# Disp_Eye.net
KiCad netlist of a schematic drawn in Altium Designer
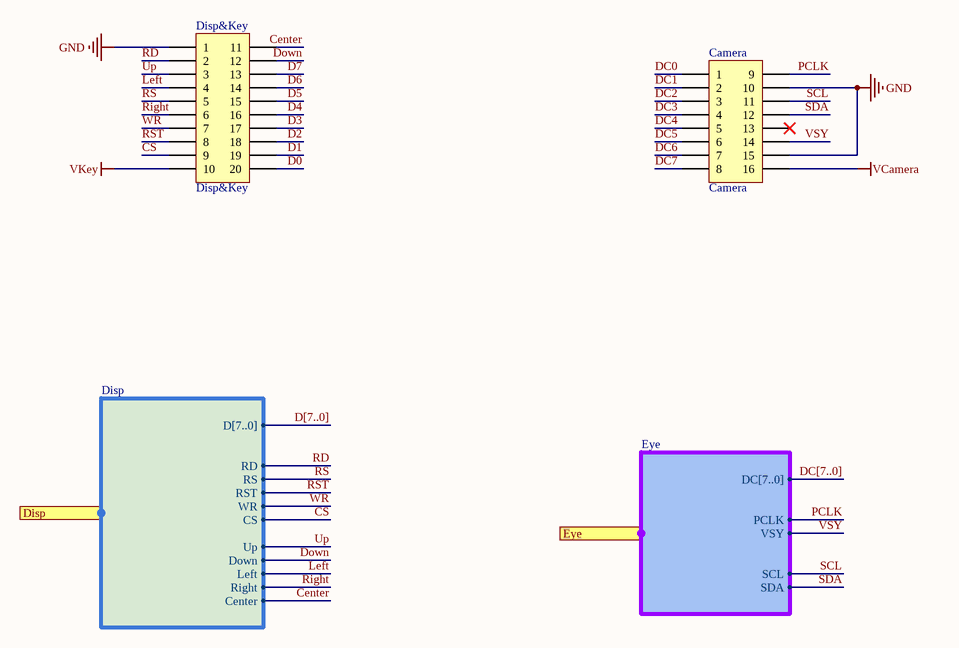
[diagram p0: Disp&Eye.SchDoc]

(export (version "E")
  (design (tool "Eeschema 10.0.6"))
  (components
    (comp (ref "Camera")
      (value "Camera")
      (footprint "HDR2X8_CEN")
      (description "Header, 8-Pin, Dual row")
      (fields (field (name "PUBLISHER") "Altium Limited"))
      (libsource (lib "Miscellaneous Connectors") (part "Header 8X2A"))
    )
    (comp (ref "Disp&Key")
      (value "Disp&Key")
      (footprint "HDR2X10_CEN")
      (description "Header, 10-Pin, Dual row")
      (fields (field (name "PUBLISHER") "Altium Limited"))
      (libsource (lib "Miscellaneous Connectors") (part "Header 10X2A"))
    )
  )
  (nets
    (net (code "3") (name "/CS") (class "Default")
      (node (ref "Disp&Key") (pin "9") (pinfunction "9_9") (pintype "passive"))
    )
    (net (code "4") (name "/Center") (class "Default")
      (node (ref "Disp&Key") (pin "11") (pinfunction "11_11") (pintype "passive"))
    )
    (net (code "5") (name "/D0") (class "Default")
      (node (ref "Disp&Key") (pin "20") (pinfunction "20_20") (pintype "passive"))
    )
    (net (code "6") (name "/D1") (class "Default")
      (node (ref "Disp&Key") (pin "19") (pinfunction "19_19") (pintype "passive"))
    )
    (net (code "7") (name "/D2") (class "Default")
      (node (ref "Disp&Key") (pin "18") (pinfunction "18_18") (pintype "passive"))
    )
    (net (code "8") (name "/D3") (class "Default")
      (node (ref "Disp&Key") (pin "17") (pinfunction "17_17") (pintype "passive"))
    )
    (net (code "9") (name "/D4") (class "Default")
      (node (ref "Disp&Key") (pin "16") (pinfunction "16_16") (pintype "passive"))
    )
    (net (code "10") (name "/D5") (class "Default")
      (node (ref "Disp&Key") (pin "15") (pinfunction "15_15") (pintype "passive"))
    )
    (net (code "11") (name "/D6") (class "Default")
      (node (ref "Disp&Key") (pin "14") (pinfunction "14_14") (pintype "passive"))
    )
    (net (code "12") (name "/D7") (class "Default")
      (node (ref "Disp&Key") (pin "13") (pinfunction "13_13") (pintype "passive"))
    )
    (net (code "13") (name "/DC0") (class "Default")
      (node (ref "Camera") (pin "1") (pinfunction "1_1") (pintype "passive"))
    )
    (net (code "14") (name "/DC1") (class "Default")
      (node (ref "Camera") (pin "2") (pinfunction "2_2") (pintype "passive"))
    )
    (net (code "15") (name "/DC2") (class "Default")
      (node (ref "Camera") (pin "3") (pinfunction "3_3") (pintype "passive"))
    )
    (net (code "16") (name "/DC3") (class "Default")
      (node (ref "Camera") (pin "4") (pinfunction "4_4") (pintype "passive"))
    )
    (net (code "17") (name "/DC4") (class "Default")
      (node (ref "Camera") (pin "5") (pinfunction "5_5") (pintype "passive"))
    )
    (net (code "18") (name "/DC5") (class "Default")
      (node (ref "Camera") (pin "6") (pinfunction "6_6") (pintype "passive"))
    )
    (net (code "19") (name "/DC6") (class "Default")
      (node (ref "Camera") (pin "7") (pinfunction "7_7") (pintype "passive"))
    )
    (net (code "20") (name "/DC7") (class "Default")
      (node (ref "Camera") (pin "8") (pinfunction "8_8") (pintype "passive"))
    )
    (net (code "22") (name "/Down") (class "Default")
      (node (ref "Disp&Key") (pin "12") (pinfunction "12_12") (pintype "passive"))
    )
    (net (code "24") (name "/Left") (class "Default")
      (node (ref "Disp&Key") (pin "4") (pinfunction "4_4") (pintype "passive"))
    )
    (net (code "25") (name "/PCLK") (class "Default")
      (node (ref "Camera") (pin "9") (pinfunction "9_9") (pintype "passive"))
    )
    (net (code "26") (name "/RD") (class "Default")
      (node (ref "Disp&Key") (pin "2") (pinfunction "2_2") (pintype "passive"))
    )
    (net (code "27") (name "/RS") (class "Default")
      (node (ref "Disp&Key") (pin "5") (pinfunction "5_5") (pintype "passive"))
    )
    (net (code "28") (name "/RST") (class "Default")
      (node (ref "Disp&Key") (pin "8") (pinfunction "8_8") (pintype "passive"))
    )
    (net (code "29") (name "/Right") (class "Default")
      (node (ref "Disp&Key") (pin "6") (pinfunction "6_6") (pintype "passive"))
    )
    (net (code "30") (name "/SCL") (class "Default")
      (node (ref "Camera") (pin "11") (pinfunction "11_11") (pintype "passive"))
    )
    (net (code "31") (name "/SDA") (class "Default")
      (node (ref "Camera") (pin "12") (pinfunction "12_12") (pintype "passive"))
    )
    (net (code "32") (name "/Up") (class "Default")
      (node (ref "Disp&Key") (pin "3") (pinfunction "3_3") (pintype "passive"))
    )
    (net (code "33") (name "/VSY") (class "Default")
      (node (ref "Camera") (pin "14") (pinfunction "14_14") (pintype "passive"))
    )
    (net (code "34") (name "/WR") (class "Default")
      (node (ref "Disp&Key") (pin "7") (pinfunction "7_7") (pintype "passive"))
    )
    (net (code "37") (name "GND") (class "Default")
      (node (ref "Camera") (pin "10") (pinfunction "10_10") (pintype "passive"))
      (node (ref "Camera") (pin "15") (pinfunction "15_15") (pintype "passive"))
      (node (ref "Disp&Key") (pin "1") (pinfunction "1_1") (pintype "passive"))
    )
    (net (code "38") (name "VCamera") (class "Default")
      (node (ref "Camera") (pin "16") (pinfunction "16_16") (pintype "passive"))
    )
    (net (code "39") (name "VKey") (class "Default")
      (node (ref "Disp&Key") (pin "10") (pinfunction "10_10") (pintype "passive"))
    )
    (net (code "40") (name "unconnected-(Camera-Pad13)") (class "Default")
      (node (ref "Camera") (pin "13") (pinfunction "13_13") (pintype "passive+no_connect"))
    )
  )
)
